# 16gpio_misc.net
KiCad netlist of a schematic drawn in Altium Designer
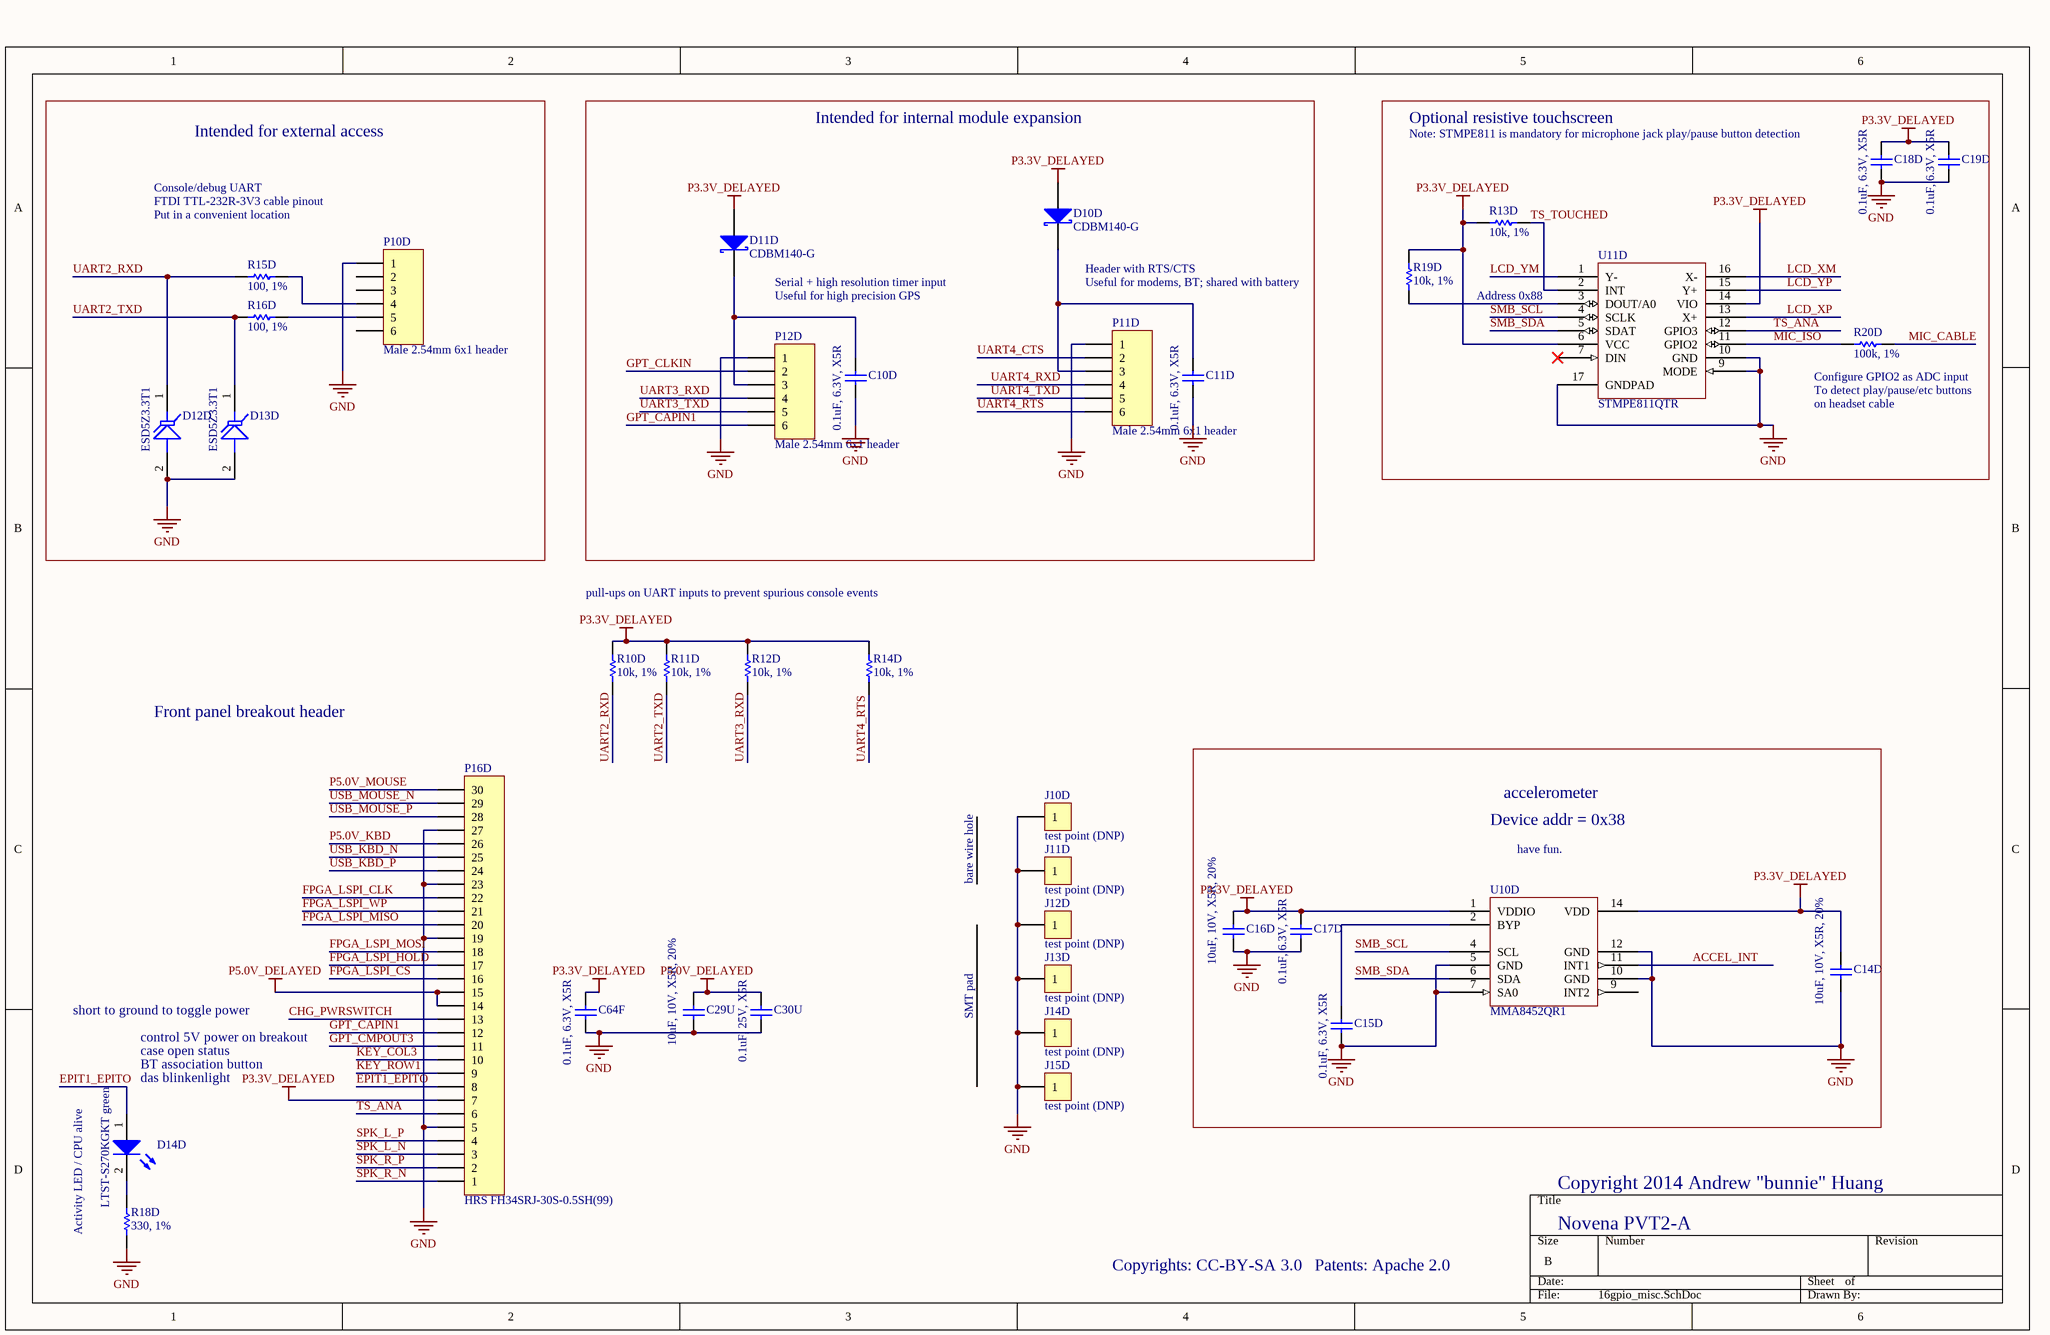
[diagram p0: 16gpio_misc.SchDoc]

(export (version "E")
  (design (tool "Eeschema 10.0.6"))
  (components
    (comp (ref "C10D")
      (value "0.1uF, 6.3V, X5R")
      (footprint "CAPC0603N_B")
      (description "Capacitor (Semiconductor SIM Model)")
      (fields (field (name "PUBLISHER") "Altium Limited"))
      (libsource (lib "Miscellaneous Devices") (part "Cap Semi"))
    )
    (comp (ref "C11D")
      (value "0.1uF, 6.3V, X5R")
      (footprint "CAPC0603N_B")
      (description "Capacitor (Semiconductor SIM Model)")
      (fields (field (name "PUBLISHER") "Altium Limited"))
      (libsource (lib "Miscellaneous Devices") (part "Cap Semi"))
    )
    (comp (ref "C14D")
      (value "10uF, 10V, X5R, 20%")
      (footprint "CAPC1608N")
      (description "Capacitor (Semiconductor SIM Model)")
      (fields (field (name "PUBLISHER") "Altium Limited"))
      (libsource (lib "Miscellaneous Devices") (part "Cap Semi"))
    )
    (comp (ref "C15D")
      (value "0.1uF, 6.3V, X5R")
      (footprint "CAPC0603N_B")
      (description "Capacitor (Semiconductor SIM Model)")
      (fields (field (name "PUBLISHER") "Altium Limited"))
      (libsource (lib "Miscellaneous Devices") (part "Cap Semi"))
    )
    (comp (ref "C16D")
      (value "10uF, 10V, X5R, 20%")
      (footprint "CAPC1608N")
      (description "Capacitor (Semiconductor SIM Model)")
      (fields (field (name "PUBLISHER") "Altium Limited"))
      (libsource (lib "Miscellaneous Devices") (part "Cap Semi"))
    )
    (comp (ref "C17D")
      (value "0.1uF, 6.3V, X5R")
      (footprint "CAPC0603N_B")
      (description "Capacitor (Semiconductor SIM Model)")
      (fields (field (name "PUBLISHER") "Altium Limited"))
      (libsource (lib "Miscellaneous Devices") (part "Cap Semi"))
    )
    (comp (ref "C18D")
      (value "0.1uF, 6.3V, X5R")
      (footprint "CAPC0603N_B")
      (description "Capacitor (Semiconductor SIM Model)")
      (fields (field (name "PUBLISHER") "Altium Limited"))
      (libsource (lib "Miscellaneous Devices") (part "Cap Semi"))
    )
    (comp (ref "C19D")
      (value "0.1uF, 6.3V, X5R")
      (footprint "CAPC0603N_B")
      (description "Capacitor (Semiconductor SIM Model)")
      (fields (field (name "PUBLISHER") "Altium Limited"))
      (libsource (lib "Miscellaneous Devices") (part "Cap Semi"))
    )
    (comp (ref "C29U")
      (value "10uF, 10V, X5R, 20%")
      (footprint "CAPC1608N")
      (description "Capacitor (Semiconductor SIM Model)")
      (fields (field (name "PUBLISHER") "Altium Limited"))
      (libsource (lib "Miscellaneous Devices") (part "Cap Semi"))
    )
    (comp (ref "C30U")
      (value "0.1uF, 25V, X5R")
      (footprint "CAPC1005N")
      (description "Capacitor (Semiconductor SIM Model)")
      (fields (field (name "PUBLISHER") "Altium Limited"))
      (libsource (lib "Miscellaneous Devices") (part "Cap Semi"))
    )
    (comp (ref "C64F")
      (value "0.1uF, 6.3V, X5R")
      (footprint "CAPC0603N_B")
      (description "Capacitor (Semiconductor SIM Model)")
      (fields (field (name "PUBLISHER") "Altium Limited"))
      (libsource (lib "Miscellaneous Devices") (part "Cap Semi"))
    )
    (comp (ref "D10D")
      (value "CDBM140-G")
      (footprint "SOD123")
      (description "Schottky Diode")
      (fields (field (name "PUBLISHER") "Altium Limited"))
      (libsource (lib "Miscellaneous Devices") (part "D Schottky"))
    )
    (comp (ref "D11D")
      (value "CDBM140-G")
      (footprint "SOD123")
      (description "Schottky Diode")
      (fields (field (name "PUBLISHER") "Altium Limited"))
      (libsource (lib "Miscellaneous Devices") (part "D Schottky"))
    )
    (comp (ref "D12D")
      (value "ESD5Z3.3T1")
      (footprint "SOD-523")
      (description "On Semi 3.3V standoff TVS diode")
      (fields (field (name "PUBLISHER") "Altium Limited"))
      (libsource (lib "Miscellaneous Devices") (part "Tranzorb"))
    )
    (comp (ref "D13D")
      (value "ESD5Z3.3T1")
      (footprint "SOD-523")
      (description "On Semi 3.3V standoff TVS diode")
      (fields (field (name "PUBLISHER") "Altium Limited"))
      (libsource (lib "Miscellaneous Devices") (part "Tranzorb"))
    )
    (comp (ref "D14D")
      (value "LTST-S270KGKT green")
      (footprint "CD1608-0603")
      (description "Green R/A LED, 0603 package")
      (fields (field (name "PUBLISHER") "Altium Limited"))
      (libsource (lib "Miscellaneous Devices") (part "LED2"))
    )
    (comp (ref "J10D")
      (value "test point (DNP)")
      (footprint "TP_HOLE")
      (description "Connector")
      (libsource (lib "*") (part "CON1"))
    )
    (comp (ref "J11D")
      (value "test point (DNP)")
      (footprint "TP_HOLE")
      (description "Connector")
      (libsource (lib "*") (part "CON1"))
    )
    (comp (ref "J12D")
      (value "test point (DNP)")
      (footprint "TP_SMT_38mil")
      (description "Connector")
      (libsource (lib "*") (part "CON1"))
    )
    (comp (ref "J13D")
      (value "test point (DNP)")
      (footprint "TP_SMT_38mil")
      (description "Connector")
      (libsource (lib "*") (part "CON1"))
    )
    (comp (ref "J14D")
      (value "test point (DNP)")
      (footprint "TP_SMT_38mil")
      (description "Connector")
      (libsource (lib "*") (part "CON1"))
    )
    (comp (ref "J15D")
      (value "test point (DNP)")
      (footprint "TP_SMT_38mil")
      (description "Connector")
      (libsource (lib "*") (part "CON1"))
    )
    (comp (ref "P10D")
      (value "Male 2.54mm 6x1 header")
      (footprint "HDR1X6")
      (description "Header, 6-Pin")
      (fields (field (name "PUBLISHER") "Altium Limited"))
      (libsource (lib "Miscellaneous Connectors") (part "Header 6"))
    )
    (comp (ref "P11D")
      (value "Male 2.54mm 6x1 header")
      (footprint "HDR1X6")
      (description "Header, 6-Pin")
      (fields (field (name "PUBLISHER") "Altium Limited"))
      (libsource (lib "Miscellaneous Connectors") (part "Header 6"))
    )
    (comp (ref "P12D")
      (value "Male 2.54mm 6x1 header")
      (footprint "HDR1X6")
      (description "Header, 6-Pin")
      (fields (field (name "PUBLISHER") "Altium Limited"))
      (libsource (lib "Miscellaneous Connectors") (part "Header 6"))
    )
    (comp (ref "P16D")
      (value "HRS FH34SRJ-30S-0.5SH(99)")
      (footprint "HRS_FH34SRJ-30S-0.5SH")
      (description "Header, 30-Pin")
      (fields (field (name "PUBLISHER") "Altium Limited"))
      (libsource (lib "Miscellaneous Connectors") (part "Header 30"))
    )
    (comp (ref "R10D")
      (value "10k, 1%")
      (footprint "RESC1005N")
      (description "Resistor")
      (fields (field (name "PUBLISHER") "Altium Limited"))
      (libsource (lib "Miscellaneous Devices") (part "Res1"))
    )
    (comp (ref "R11D")
      (value "10k, 1%")
      (footprint "RESC1005N")
      (description "Resistor")
      (fields (field (name "PUBLISHER") "Altium Limited"))
      (libsource (lib "Miscellaneous Devices") (part "Res1"))
    )
    (comp (ref "R12D")
      (value "10k, 1%")
      (footprint "RESC1005N")
      (description "Resistor")
      (fields (field (name "PUBLISHER") "Altium Limited"))
      (libsource (lib "Miscellaneous Devices") (part "Res1"))
    )
    (comp (ref "R13D")
      (value "10k, 1%")
      (footprint "RESC1005N")
      (description "Resistor")
      (fields (field (name "PUBLISHER") "Altium Limited"))
      (libsource (lib "Miscellaneous Devices") (part "Res1"))
    )
    (comp (ref "R14D")
      (value "10k, 1%")
      (footprint "RESC1005N")
      (description "Resistor")
      (fields (field (name "PUBLISHER") "Altium Limited"))
      (libsource (lib "Miscellaneous Devices") (part "Res1"))
    )
    (comp (ref "R15D")
      (value "100, 1%")
      (footprint "RESC1005N")
      (description "Resistor")
      (fields (field (name "PUBLISHER") "Altium Limited"))
      (libsource (lib "Miscellaneous Devices") (part "Res1"))
    )
    (comp (ref "R16D")
      (value "100, 1%")
      (footprint "RESC1005N")
      (description "Resistor")
      (fields (field (name "PUBLISHER") "Altium Limited"))
      (libsource (lib "Miscellaneous Devices") (part "Res1"))
    )
    (comp (ref "R18D")
      (value "330, 1%")
      (footprint "RESC1005N")
      (description "Resistor")
      (fields (field (name "PUBLISHER") "Altium Limited"))
      (libsource (lib "Miscellaneous Devices") (part "Res1"))
    )
    (comp (ref "R19D")
      (value "10k, 1%")
      (footprint "RESC1005N")
      (description "Resistor")
      (fields (field (name "PUBLISHER") "Altium Limited"))
      (libsource (lib "Miscellaneous Devices") (part "Res1"))
    )
    (comp (ref "R20D")
      (value "100k, 1%")
      (footprint "RESC1005N")
      (description "Resistor")
      (fields (field (name "PUBLISHER") "Altium Limited"))
      (libsource (lib "Miscellaneous Devices") (part "Res1"))
    )
    (comp (ref "U10D")
      (value "MMA8452QR1")
      (footprint "FSC_QFN_3x3x1_16_2077-02")
      (description "3-axis, 12-bit/8-bit digital accelerometer")
      (libsource (lib "commonsch") (part "MMA8452QR1"))
    )
    (comp (ref "U11D")
      (value "STMPE811QTR")
      (footprint "QFN50P300X300-16V2N")
      (description "4-wire resistive touchscreen controller")
      (libsource (lib "commonsch") (part "STMPE610"))
    )
  )
  (nets
    (net (code "1") (name "/ACCEL_INT") (class "Default")
      (node (ref "U10D") (pin "11") (pinfunction "INT1_11") (pintype "output"))
    )
    (net (code "2") (name "/CHG_PWRSWITCH") (class "Default")
      (node (ref "P16D") (pin "13") (pinfunction "13_13") (pintype "passive"))
    )
    (net (code "3") (name "/EPIT1_EPITO") (class "Default")
      (node (ref "D14D") (pin "1") (pinfunction "A_1") (pintype "passive"))
      (node (ref "P16D") (pin "8") (pinfunction "8_8") (pintype "passive"))
    )
    (net (code "4") (name "/FPGA_LSPI_CLK") (class "Default")
      (node (ref "P16D") (pin "22") (pinfunction "22_22") (pintype "passive"))
    )
    (net (code "5") (name "/FPGA_LSPI_CS") (class "Default")
      (node (ref "P16D") (pin "16") (pinfunction "16_16") (pintype "passive"))
    )
    (net (code "6") (name "/FPGA_LSPI_HOLD") (class "Default")
      (node (ref "P16D") (pin "17") (pinfunction "17_17") (pintype "passive"))
    )
    (net (code "7") (name "/FPGA_LSPI_MISO") (class "Default")
      (node (ref "P16D") (pin "20") (pinfunction "20_20") (pintype "passive"))
    )
    (net (code "8") (name "/FPGA_LSPI_MOSI") (class "Default")
      (node (ref "P16D") (pin "18") (pinfunction "18_18") (pintype "passive"))
    )
    (net (code "9") (name "/FPGA_LSPI_WP") (class "Default")
      (node (ref "P16D") (pin "21") (pinfunction "21_21") (pintype "passive"))
    )
    (net (code "10") (name "/GPT_CAPIN1") (class "Default")
      (node (ref "P12D") (pin "6") (pinfunction "6_6") (pintype "passive"))
      (node (ref "P16D") (pin "12") (pinfunction "12_12") (pintype "passive"))
    )
    (net (code "11") (name "/GPT_CLKIN") (class "Default")
      (node (ref "P12D") (pin "2") (pinfunction "2_2") (pintype "passive"))
    )
    (net (code "12") (name "/GPT_CMPOUT3") (class "Default")
      (node (ref "P16D") (pin "11") (pinfunction "11_11") (pintype "passive"))
    )
    (net (code "13") (name "/KEY_COL3") (class "Default")
      (node (ref "P16D") (pin "10") (pinfunction "10_10") (pintype "passive"))
    )
    (net (code "14") (name "/KEY_ROW1") (class "Default")
      (node (ref "P16D") (pin "9") (pinfunction "9_9") (pintype "passive"))
    )
    (net (code "15") (name "/LCD_XM") (class "Default")
      (node (ref "U11D") (pin "16") (pinfunction "X-_16") (pintype "passive"))
    )
    (net (code "16") (name "/LCD_XP") (class "Default")
      (node (ref "U11D") (pin "13") (pinfunction "X+_13") (pintype "passive"))
    )
    (net (code "17") (name "/LCD_YM") (class "Default")
      (node (ref "U11D") (pin "1") (pinfunction "Y-_1") (pintype "passive"))
    )
    (net (code "18") (name "/LCD_YP") (class "Default")
      (node (ref "U11D") (pin "15") (pinfunction "Y+_15") (pintype "passive"))
    )
    (net (code "19") (name "/MIC_CABLE") (class "Default")
      (node (ref "R20D") (pin "2") (pinfunction "2_2") (pintype "passive"))
    )
    (net (code "20") (name "/MIC_ISO") (class "Default")
      (node (ref "R20D") (pin "1") (pinfunction "1_1") (pintype "passive"))
      (node (ref "U11D") (pin "11") (pinfunction "GPIO2_11") (pintype "bidirectional"))
    )
    (net (code "21") (name "/P5.0V_KBD") (class "Default")
      (node (ref "P16D") (pin "26") (pinfunction "26_26") (pintype "passive"))
    )
    (net (code "22") (name "/P5.0V_MOUSE") (class "Default")
      (node (ref "P16D") (pin "30") (pinfunction "30_30") (pintype "passive"))
    )
    (net (code "23") (name "/SMB_SCL") (class "Default")
      (node (ref "U10D") (pin "4") (pinfunction "SCL_4") (pintype "open_collector"))
      (node (ref "U11D") (pin "4") (pinfunction "SCLK_4") (pintype "bidirectional"))
    )
    (net (code "24") (name "/SMB_SDA") (class "Default")
      (node (ref "U10D") (pin "6") (pinfunction "SDA_6") (pintype "open_collector"))
      (node (ref "U11D") (pin "5") (pinfunction "SDAT_5") (pintype "bidirectional"))
    )
    (net (code "25") (name "/SPK_L_N") (class "Default")
      (node (ref "P16D") (pin "3") (pinfunction "3_3") (pintype "passive"))
    )
    (net (code "26") (name "/SPK_L_P") (class "Default")
      (node (ref "P16D") (pin "4") (pinfunction "4_4") (pintype "passive"))
    )
    (net (code "27") (name "/SPK_R_N") (class "Default")
      (node (ref "P16D") (pin "1") (pinfunction "1_1") (pintype "passive"))
    )
    (net (code "28") (name "/SPK_R_P") (class "Default")
      (node (ref "P16D") (pin "2") (pinfunction "2_2") (pintype "passive"))
    )
    (net (code "29") (name "/TS_ANA") (class "Default")
      (node (ref "P16D") (pin "6") (pinfunction "6_6") (pintype "passive"))
      (node (ref "U11D") (pin "12") (pinfunction "GPIO3_12") (pintype "bidirectional"))
    )
    (net (code "30") (name "/TS_TOUCHED") (class "Default")
      (node (ref "R13D") (pin "1") (pinfunction "1_1") (pintype "passive"))
      (node (ref "U11D") (pin "2") (pinfunction "INT_2") (pintype "open_collector"))
    )
    (net (code "31") (name "/UART2_RXD") (class "Default")
      (node (ref "D12D") (pin "1") (pinfunction "K_1") (pintype "passive"))
      (node (ref "R10D") (pin "2") (pinfunction "2_2") (pintype "passive"))
      (node (ref "R15D") (pin "2") (pinfunction "2_2") (pintype "passive"))
    )
    (net (code "32") (name "/UART2_TXD") (class "Default")
      (node (ref "D13D") (pin "1") (pinfunction "K_1") (pintype "passive"))
      (node (ref "R11D") (pin "2") (pinfunction "2_2") (pintype "passive"))
      (node (ref "R16D") (pin "2") (pinfunction "2_2") (pintype "passive"))
    )
    (net (code "33") (name "/UART3_RXD") (class "Default")
      (node (ref "P12D") (pin "4") (pinfunction "4_4") (pintype "passive"))
      (node (ref "R12D") (pin "2") (pinfunction "2_2") (pintype "passive"))
    )
    (net (code "34") (name "/UART3_TXD") (class "Default")
      (node (ref "P12D") (pin "5") (pinfunction "5_5") (pintype "passive"))
    )
    (net (code "35") (name "/UART4_CTS") (class "Default")
      (node (ref "P11D") (pin "2") (pinfunction "2_2") (pintype "passive"))
    )
    (net (code "36") (name "/UART4_RTS") (class "Default")
      (node (ref "P11D") (pin "6") (pinfunction "6_6") (pintype "passive"))
      (node (ref "R14D") (pin "2") (pinfunction "2_2") (pintype "passive"))
    )
    (net (code "37") (name "/UART4_RXD") (class "Default")
      (node (ref "P11D") (pin "4") (pinfunction "4_4") (pintype "passive"))
    )
    (net (code "38") (name "/UART4_TXD") (class "Default")
      (node (ref "P11D") (pin "5") (pinfunction "5_5") (pintype "passive"))
    )
    (net (code "39") (name "/USB_KBD_N") (class "Default")
      (node (ref "P16D") (pin "25") (pinfunction "25_25") (pintype "passive"))
    )
    (net (code "40") (name "/USB_KBD_P") (class "Default")
      (node (ref "P16D") (pin "24") (pinfunction "24_24") (pintype "passive"))
    )
    (net (code "41") (name "/USB_MOUSE_N") (class "Default")
      (node (ref "P16D") (pin "29") (pinfunction "29_29") (pintype "passive"))
    )
    (net (code "42") (name "/USB_MOUSE_P") (class "Default")
      (node (ref "P16D") (pin "28") (pinfunction "28_28") (pintype "passive"))
    )
    (net (code "43") (name "GND") (class "Default")
      (node (ref "C10D") (pin "2") (pinfunction "2_2") (pintype "passive"))
      (node (ref "C11D") (pin "2") (pinfunction "2_2") (pintype "passive"))
      (node (ref "C14D") (pin "2") (pinfunction "2_2") (pintype "passive"))
      (node (ref "C15D") (pin "2") (pinfunction "2_2") (pintype "passive"))
      (node (ref "C16D") (pin "2") (pinfunction "2_2") (pintype "passive"))
      (node (ref "C17D") (pin "2") (pinfunction "2_2") (pintype "passive"))
      (node (ref "C18D") (pin "2") (pinfunction "2_2") (pintype "passive"))
      (node (ref "C19D") (pin "2") (pinfunction "2_2") (pintype "passive"))
      (node (ref "C29U") (pin "2") (pinfunction "2_2") (pintype "passive"))
      (node (ref "C30U") (pin "2") (pinfunction "2_2") (pintype "passive"))
      (node (ref "C64F") (pin "2") (pinfunction "2_2") (pintype "passive"))
      (node (ref "D12D") (pin "2") (pinfunction "A_2") (pintype "passive"))
      (node (ref "D13D") (pin "2") (pinfunction "A_2") (pintype "passive"))
      (node (ref "J10D") (pin "1") (pinfunction "1_1") (pintype "passive"))
      (node (ref "J11D") (pin "1") (pinfunction "1_1") (pintype "passive"))
      (node (ref "J12D") (pin "1") (pinfunction "1_1") (pintype "passive"))
      (node (ref "J13D") (pin "1") (pinfunction "1_1") (pintype "passive"))
      (node (ref "J14D") (pin "1") (pinfunction "1_1") (pintype "passive"))
      (node (ref "J15D") (pin "1") (pinfunction "1_1") (pintype "passive"))
      (node (ref "P10D") (pin "1") (pinfunction "1_1") (pintype "passive"))
      (node (ref "P11D") (pin "1") (pinfunction "1_1") (pintype "passive"))
      (node (ref "P12D") (pin "1") (pinfunction "1_1") (pintype "passive"))
      (node (ref "P16D") (pin "19") (pinfunction "19_19") (pintype "passive"))
      (node (ref "P16D") (pin "23") (pinfunction "23_23") (pintype "passive"))
      (node (ref "P16D") (pin "27") (pinfunction "27_27") (pintype "passive"))
      (node (ref "P16D") (pin "5") (pinfunction "5_5") (pintype "passive"))
      (node (ref "R18D") (pin "1") (pinfunction "1_1") (pintype "passive"))
      (node (ref "U10D") (pin "10") (pinfunction "GND_10") (pintype "power_in"))
      (node (ref "U10D") (pin "12") (pinfunction "GND_12") (pintype "power_in"))
      (node (ref "U10D") (pin "5") (pinfunction "GND_5") (pintype "power_in"))
      (node (ref "U10D") (pin "7") (pinfunction "SA0_7") (pintype "input"))
      (node (ref "U11D") (pin "10") (pinfunction "GND_10") (pintype "power_in"))
      (node (ref "U11D") (pin "17") (pinfunction "GNDPAD_17") (pintype "power_in"))
      (node (ref "U11D") (pin "9") (pinfunction "MODE_9") (pintype "input"))
    )
    (net (code "44") (name "Net-(D10D-K)") (class "Default")
      (node (ref "C11D") (pin "1") (pinfunction "1_1") (pintype "passive"))
      (node (ref "D10D") (pin "2") (pinfunction "K_2") (pintype "passive"))
      (node (ref "P11D") (pin "3") (pinfunction "3_3") (pintype "passive"))
    )
    (net (code "45") (name "Net-(D11D-K)") (class "Default")
      (node (ref "C10D") (pin "1") (pinfunction "1_1") (pintype "passive"))
      (node (ref "D11D") (pin "2") (pinfunction "K_2") (pintype "passive"))
      (node (ref "P12D") (pin "3") (pinfunction "3_3") (pintype "passive"))
    )
    (net (code "46") (name "Net-(D14D-K)") (class "Default")
      (node (ref "D14D") (pin "2") (pinfunction "K_2") (pintype "passive"))
      (node (ref "R18D") (pin "2") (pinfunction "2_2") (pintype "passive"))
    )
    (net (code "47") (name "Net-(P10D-Pad4)") (class "Default")
      (node (ref "P10D") (pin "4") (pinfunction "4_4") (pintype "passive"))
      (node (ref "R15D") (pin "1") (pinfunction "1_1") (pintype "passive"))
    )
    (net (code "48") (name "Net-(P10D-Pad5)") (class "Default")
      (node (ref "P10D") (pin "5") (pinfunction "5_5") (pintype "passive"))
      (node (ref "R16D") (pin "1") (pinfunction "1_1") (pintype "passive"))
    )
    (net (code "49") (name "Net-(U10D-BYP)") (class "Default")
      (node (ref "C15D") (pin "1") (pinfunction "1_1") (pintype "passive"))
      (node (ref "U10D") (pin "2") (pinfunction "BYP_2") (pintype "passive"))
    )
    (net (code "50") (name "Net-(U11D-DOUT{slash}A0)") (class "Default")
      (node (ref "R19D") (pin "2") (pinfunction "2_2") (pintype "passive"))
      (node (ref "U11D") (pin "3") (pinfunction "DOUT/A0_3") (pintype "bidirectional"))
    )
    (net (code "51") (name "P3.3V_DELAYED") (class "Default")
      (node (ref "C14D") (pin "1") (pinfunction "1_1") (pintype "passive"))
      (node (ref "C16D") (pin "1") (pinfunction "1_1") (pintype "passive"))
      (node (ref "C17D") (pin "1") (pinfunction "1_1") (pintype "passive"))
      (node (ref "C18D") (pin "1") (pinfunction "1_1") (pintype "passive"))
      (node (ref "C19D") (pin "1") (pinfunction "1_1") (pintype "passive"))
      (node (ref "C64F") (pin "1") (pinfunction "1_1") (pintype "passive"))
      (node (ref "D10D") (pin "1") (pinfunction "A_1") (pintype "passive"))
      (node (ref "D11D") (pin "1") (pinfunction "A_1") (pintype "passive"))
      (node (ref "P16D") (pin "7") (pinfunction "7_7") (pintype "passive"))
      (node (ref "R10D") (pin "1") (pinfunction "1_1") (pintype "passive"))
      (node (ref "R11D") (pin "1") (pinfunction "1_1") (pintype "passive"))
      (node (ref "R12D") (pin "1") (pinfunction "1_1") (pintype "passive"))
      (node (ref "R13D") (pin "2") (pinfunction "2_2") (pintype "passive"))
      (node (ref "R14D") (pin "1") (pinfunction "1_1") (pintype "passive"))
      (node (ref "R19D") (pin "1") (pinfunction "1_1") (pintype "passive"))
      (node (ref "U10D") (pin "1") (pinfunction "VDDIO_1") (pintype "power_in"))
      (node (ref "U10D") (pin "14") (pinfunction "VDD_14") (pintype "power_in"))
      (node (ref "U11D") (pin "14") (pinfunction "VIO_14") (pintype "power_in"))
      (node (ref "U11D") (pin "6") (pinfunction "VCC_6") (pintype "power_in"))
    )
    (net (code "52") (name "P5.0V_DELAYED") (class "Default")
      (node (ref "C29U") (pin "1") (pinfunction "1_1") (pintype "passive"))
      (node (ref "C30U") (pin "1") (pinfunction "1_1") (pintype "passive"))
      (node (ref "P16D") (pin "14") (pinfunction "14_14") (pintype "passive"))
      (node (ref "P16D") (pin "15") (pinfunction "15_15") (pintype "passive"))
    )
    (net (code "53") (name "unconnected-(P10D-Pad2)") (class "Default")
      (node (ref "P10D") (pin "2") (pinfunction "2_2") (pintype "passive"))
    )
    (net (code "54") (name "unconnected-(P10D-Pad3)") (class "Default")
      (node (ref "P10D") (pin "3") (pinfunction "3_3") (pintype "passive"))
    )
    (net (code "55") (name "unconnected-(P10D-Pad6)") (class "Default")
      (node (ref "P10D") (pin "6") (pinfunction "6_6") (pintype "passive"))
    )
    (net (code "56") (name "unconnected-(U10D-INT2-Pad9)") (class "Default")
      (node (ref "U10D") (pin "9") (pinfunction "INT2_9") (pintype "output"))
    )
    (net (code "57") (name "unconnected-(U11D-DIN-Pad7)") (class "Default")
      (node (ref "U11D") (pin "7") (pinfunction "DIN_7") (pintype "input+no_connect"))
    )
  )
)
